# keyboard.net
KiCad netlist of a schematic drawn in EAGLE
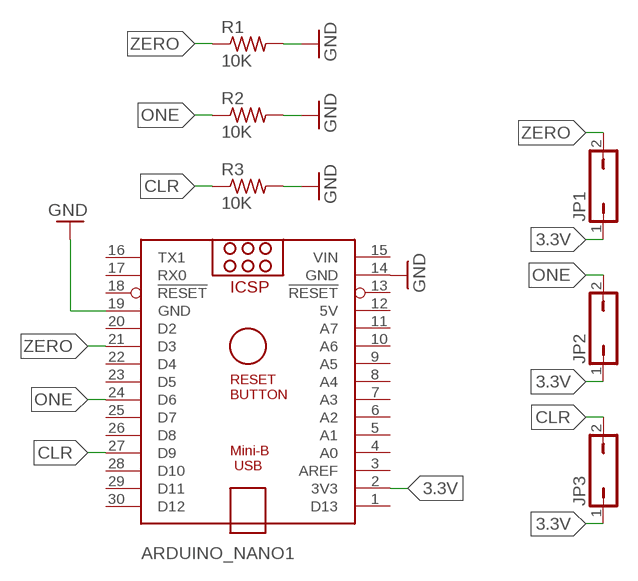
[diagram p0: schematic, sheet 1]

(export (version "E")
  (design (tool "Eeschema 10.0.6"))
  (components
    (comp (ref "ARDUINO_NANO1")
      (value "ARDUINO_NANO")
      (footprint "eagle-import:ARDUINO_NANO")
      (libsource (lib "eagle-import") (part "ARDUINO_NANO"))
    )
    (comp (ref "JP1")
      (value "JP1Q")
      (footprint "eagle-import:JP1")
      (libsource (lib "eagle-import") (part "JP1Q"))
    )
    (comp (ref "JP2")
      (value "JP1Q")
      (footprint "eagle-import:JP1")
      (libsource (lib "eagle-import") (part "JP1Q"))
    )
    (comp (ref "JP3")
      (value "JP1Q")
      (footprint "eagle-import:JP1")
      (libsource (lib "eagle-import") (part "JP1Q"))
    )
    (comp (ref "R1")
      (value "10K")
      (footprint "eagle-import:0207_12")
      (libsource (lib "eagle-import") (part "R-US_0207/12"))
    )
    (comp (ref "R2")
      (value "10K")
      (footprint "eagle-import:0207_12")
      (libsource (lib "eagle-import") (part "R-US_0207/12"))
    )
    (comp (ref "R3")
      (value "10K")
      (footprint "eagle-import:0207_12")
      (libsource (lib "eagle-import") (part "R-US_0207/12"))
    )
  )
  (nets
    (net (code "1") (name "/5V") (class "Default")
      (node (ref "ARDUINO_NANO1") (pin "12") (pinfunction "5V_12") (pintype "power_in"))
    )
    (net (code "2") (name "/VIN") (class "Default")
      (node (ref "ARDUINO_NANO1") (pin "15") (pinfunction "VIN_15") (pintype "power_in"))
    )
    (net (code "3") (name "3.3V") (class "Default")
      (node (ref "ARDUINO_NANO1") (pin "2") (pinfunction "3V3_2") (pintype "output"))
      (node (ref "JP1") (pin "1") (pinfunction "1_1") (pintype "passive"))
      (node (ref "JP2") (pin "1") (pinfunction "1_1") (pintype "passive"))
      (node (ref "JP3") (pin "1") (pinfunction "1_1") (pintype "passive"))
    )
    (net (code "4") (name "CLR") (class "Default")
      (node (ref "ARDUINO_NANO1") (pin "27") (pinfunction "D9_27") (pintype "bidirectional"))
      (node (ref "JP3") (pin "2") (pinfunction "2_2") (pintype "passive"))
      (node (ref "R3") (pin "1") (pinfunction "1_1") (pintype "passive"))
    )
    (net (code "5") (name "GND") (class "Default")
      (node (ref "ARDUINO_NANO1") (pin "14") (pinfunction "GND_14") (pintype "power_in"))
      (node (ref "ARDUINO_NANO1") (pin "19") (pinfunction "GND_19") (pintype "power_in"))
      (node (ref "R1") (pin "2") (pinfunction "2_2") (pintype "passive"))
      (node (ref "R2") (pin "2") (pinfunction "2_2") (pintype "passive"))
      (node (ref "R3") (pin "2") (pinfunction "2_2") (pintype "passive"))
    )
    (net (code "6") (name "ONE") (class "Default")
      (node (ref "ARDUINO_NANO1") (pin "24") (pinfunction "D6_24") (pintype "bidirectional"))
      (node (ref "JP2") (pin "2") (pinfunction "2_2") (pintype "passive"))
      (node (ref "R2") (pin "1") (pinfunction "1_1") (pintype "passive"))
    )
    (net (code "7") (name "ZERO") (class "Default")
      (node (ref "ARDUINO_NANO1") (pin "21") (pinfunction "D3_21") (pintype "bidirectional"))
      (node (ref "JP1") (pin "2") (pinfunction "2_2") (pintype "passive"))
      (node (ref "R1") (pin "1") (pinfunction "1_1") (pintype "passive"))
    )
    (net (code "8") (name "unconnected-(ARDUINO_NANO1-A0-Pad4)") (class "Default")
      (node (ref "ARDUINO_NANO1") (pin "4") (pinfunction "A0_4") (pintype "bidirectional"))
    )
    (net (code "9") (name "unconnected-(ARDUINO_NANO1-A1-Pad5)") (class "Default")
      (node (ref "ARDUINO_NANO1") (pin "5") (pinfunction "A1_5") (pintype "bidirectional"))
    )
    (net (code "10") (name "unconnected-(ARDUINO_NANO1-A2-Pad6)") (class "Default")
      (node (ref "ARDUINO_NANO1") (pin "6") (pinfunction "A2_6") (pintype "bidirectional"))
    )
    (net (code "11") (name "unconnected-(ARDUINO_NANO1-A3-Pad7)") (class "Default")
      (node (ref "ARDUINO_NANO1") (pin "7") (pinfunction "A3_7") (pintype "bidirectional"))
    )
    (net (code "12") (name "unconnected-(ARDUINO_NANO1-A4-Pad8)") (class "Default")
      (node (ref "ARDUINO_NANO1") (pin "8") (pinfunction "A4_8") (pintype "bidirectional"))
    )
    (net (code "13") (name "unconnected-(ARDUINO_NANO1-A5-Pad9)") (class "Default")
      (node (ref "ARDUINO_NANO1") (pin "9") (pinfunction "A5_9") (pintype "bidirectional"))
    )
    (net (code "14") (name "unconnected-(ARDUINO_NANO1-A6-Pad10)") (class "Default")
      (node (ref "ARDUINO_NANO1") (pin "10") (pinfunction "A6_10") (pintype "bidirectional"))
    )
    (net (code "15") (name "unconnected-(ARDUINO_NANO1-A7-Pad11)") (class "Default")
      (node (ref "ARDUINO_NANO1") (pin "11") (pinfunction "A7_11") (pintype "bidirectional"))
    )
    (net (code "16") (name "unconnected-(ARDUINO_NANO1-AREF-Pad3)") (class "Default")
      (node (ref "ARDUINO_NANO1") (pin "3") (pinfunction "AREF_3") (pintype "input"))
    )
    (net (code "17") (name "unconnected-(ARDUINO_NANO1-D2-Pad20)") (class "Default")
      (node (ref "ARDUINO_NANO1") (pin "20") (pinfunction "D2_20") (pintype "bidirectional"))
    )
    (net (code "18") (name "unconnected-(ARDUINO_NANO1-D4-Pad22)") (class "Default")
      (node (ref "ARDUINO_NANO1") (pin "22") (pinfunction "D4_22") (pintype "bidirectional"))
    )
    (net (code "19") (name "unconnected-(ARDUINO_NANO1-D5-Pad23)") (class "Default")
      (node (ref "ARDUINO_NANO1") (pin "23") (pinfunction "D5_23") (pintype "bidirectional"))
    )
    (net (code "20") (name "unconnected-(ARDUINO_NANO1-D7-Pad25)") (class "Default")
      (node (ref "ARDUINO_NANO1") (pin "25") (pinfunction "D7_25") (pintype "bidirectional"))
    )
    (net (code "21") (name "unconnected-(ARDUINO_NANO1-D8-Pad26)") (class "Default")
      (node (ref "ARDUINO_NANO1") (pin "26") (pinfunction "D8_26") (pintype "bidirectional"))
    )
    (net (code "22") (name "unconnected-(ARDUINO_NANO1-D10-Pad28)") (class "Default")
      (node (ref "ARDUINO_NANO1") (pin "28") (pinfunction "D10_28") (pintype "bidirectional"))
    )
    (net (code "23") (name "unconnected-(ARDUINO_NANO1-D11-Pad29)") (class "Default")
      (node (ref "ARDUINO_NANO1") (pin "29") (pinfunction "D11_29") (pintype "bidirectional"))
    )
    (net (code "24") (name "unconnected-(ARDUINO_NANO1-D12-Pad30)") (class "Default")
      (node (ref "ARDUINO_NANO1") (pin "30") (pinfunction "D12_30") (pintype "bidirectional"))
    )
    (net (code "25") (name "unconnected-(ARDUINO_NANO1-D13-Pad1)") (class "Default")
      (node (ref "ARDUINO_NANO1") (pin "1") (pinfunction "D13_1") (pintype "bidirectional"))
    )
    (net (code "26") (name "unconnected-(ARDUINO_NANO1-RX0-Pad17)") (class "Default")
      (node (ref "ARDUINO_NANO1") (pin "17") (pinfunction "RX0_17") (pintype "bidirectional"))
    )
    (net (code "27") (name "unconnected-(ARDUINO_NANO1-TX1-Pad16)") (class "Default")
      (node (ref "ARDUINO_NANO1") (pin "16") (pinfunction "TX1_16") (pintype "bidirectional"))
    )
    (net (code "28") (name "unconnected-(ARDUINO_NANO1-~{RESET}-Pad13)") (class "Default")
      (node (ref "ARDUINO_NANO1") (pin "13") (pinfunction "~{RESET}_13") (pintype "input"))
    )
    (net (code "29") (name "unconnected-(ARDUINO_NANO1-~{RESET}-Pad18)") (class "Default")
      (node (ref "ARDUINO_NANO1") (pin "18") (pinfunction "~{RESET}_18") (pintype "input"))
    )
  )
)
